# TPS552882_SCH.net
KiCad netlist of a schematic drawn in Altium Designer
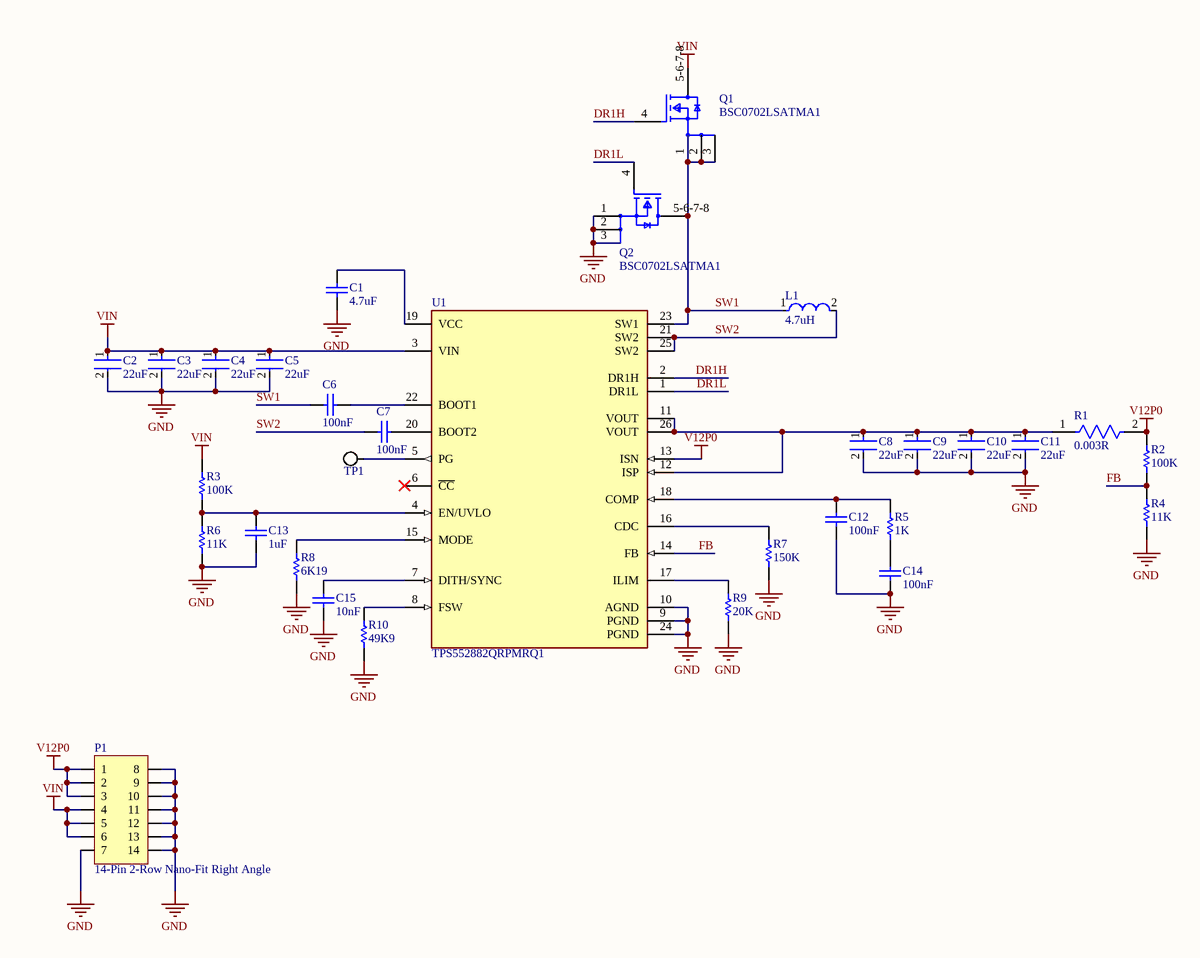
[diagram p0: TPS552882_SCH.SchDoc]

(export (version "E")
  (design (tool "Eeschema 10.0.6"))
  (components
    (comp (ref "C1")
      (value "4.7uF")
      (footprint "CAPC1608X87X35NL15T15")
      (description "C0603C475K8PACTU\r\n4.7uf 0603")
      (fields (field (name "PART NUMBER") "C0603C475K8PACTU") (field (name "MANUFACTURER") "Kemet"))
      (libsource (lib "Altium Content Vault") (part "CAP"))
    )
    (comp (ref "C2")
      (value "22uF")
      (footprint "FP-GRM32E-0_3-0_2-MFG")
      (fields (field (name "VOLTAGE") "25V") (field (name "TOLERANCE") "10%"))
      (libsource (lib "Altium Content Vault") (part "02cd4be3c70576c341d710602a673aa"))
    )
    (comp (ref "C3")
      (value "22uF")
      (footprint "FP-GRM32E-0_3-0_2-MFG")
      (fields (field (name "VOLTAGE") "25V") (field (name "TOLERANCE") "10%"))
      (libsource (lib "Altium Content Vault") (part "02cd4be3c70576c341d710602a673aa"))
    )
    (comp (ref "C4")
      (value "22uF")
      (footprint "FP-GRM32E-0_3-0_2-MFG")
      (fields (field (name "VOLTAGE") "25V") (field (name "TOLERANCE") "10%"))
      (libsource (lib "Altium Content Vault") (part "02cd4be3c70576c341d710602a673aa"))
    )
    (comp (ref "C5")
      (value "22uF")
      (footprint "FP-GRM32E-0_3-0_2-MFG")
      (fields (field (name "VOLTAGE") "25V") (field (name "TOLERANCE") "10%"))
      (libsource (lib "Altium Content Vault") (part "02cd4be3c70576c341d710602a673aa"))
    )
    (comp (ref "C6")
      (value "100nF")
      (footprint "0603")
      (description "CAP 100nF 100V ±10% 0603 (1608 Metric) Thickness 1mm SMD")
      (fields (field (name "TOLERANCE") "Â±10%"))
      (libsource (lib "TAUV-Lib") (part "100nF 0603"))
    )
    (comp (ref "C7")
      (value "100nF")
      (footprint "0603")
      (description "CAP 100nF 100V ±10% 0603 (1608 Metric) Thickness 1mm SMD")
      (fields (field (name "TOLERANCE") "Â±10%"))
      (libsource (lib "TAUV-Lib") (part "100nF 0603"))
    )
    (comp (ref "C8")
      (value "22uF")
      (footprint "FP-GRM32E-0_3-0_2-MFG")
      (fields (field (name "VOLTAGE") "25V") (field (name "TOLERANCE") "10%"))
      (libsource (lib "Altium Content Vault") (part "02cd4be3c70576c341d710602a673aa"))
    )
    (comp (ref "C9")
      (value "22uF")
      (footprint "FP-GRM32E-0_3-0_2-MFG")
      (fields (field (name "VOLTAGE") "25V") (field (name "TOLERANCE") "10%"))
      (libsource (lib "Altium Content Vault") (part "02cd4be3c70576c341d710602a673aa"))
    )
    (comp (ref "C10")
      (value "22uF")
      (footprint "FP-GRM32E-0_3-0_2-MFG")
      (fields (field (name "VOLTAGE") "25V") (field (name "TOLERANCE") "10%"))
      (libsource (lib "Altium Content Vault") (part "02cd4be3c70576c341d710602a673aa"))
    )
    (comp (ref "C11")
      (value "22uF")
      (footprint "FP-GRM32E-0_3-0_2-MFG")
      (fields (field (name "VOLTAGE") "25V") (field (name "TOLERANCE") "10%"))
      (libsource (lib "Altium Content Vault") (part "02cd4be3c70576c341d710602a673aa"))
    )
    (comp (ref "C12")
      (value "100nF")
      (footprint "0603")
      (description "CAP 100nF 100V ±10% 0603 (1608 Metric) Thickness 1mm SMD")
      (fields (field (name "TOLERANCE") "Â±10%"))
      (libsource (lib "TAUV-Lib") (part "100nF 0603"))
    )
    (comp (ref "C13")
      (value "1uF")
      (footprint "0603")
      (description "CAP 1uF 25V ±10% 0603 (1608 Metric) Thickness 1mm SMD")
      (fields (field (name "TOLERANCE") "Â±10%"))
      (libsource (lib "TAUV-Lib") (part "1uF 0603"))
    )
    (comp (ref "C14")
      (value "100nF")
      (footprint "0603")
      (description "CAP 100nF 100V ±10% 0603 (1608 Metric) Thickness 1mm SMD")
      (fields (field (name "TOLERANCE") "Â±10%"))
      (libsource (lib "TAUV-Lib") (part "100nF 0603"))
    )
    (comp (ref "C15")
      (value "10nF")
      (footprint "CAPC1608X90X35ML10T15")
      (fields
        (field (name "VOLTAGE") "50V")
        (field (name "TOLERANCE") "10%")
        (field (name "MANUFACTURER") "Murata")
      )
      (libsource (lib "Altium Content Vault") (part "CAP-NP-2"))
    )
    (comp (ref "L1")
      (value "4.7uH")
      (footprint "FP-IHLP-5050EZ-FP_3_226x4-MFG")
      (description "Commercial Inductors, High Saturation Series 4.7uH 12A 15mΩ 20%\r\nIHLP5050EZER4R7M01")
      (fields (field (name "TOLERANCE") "20%"))
      (libsource (lib "Altium Content Vault") (part "725321dda6339637d4d059423bc1c3c"))
    )
    (comp (ref "P1")
      (value "14-Pin 2-Row Nano-Fit Right Angle")
      (footprint "MOLEX NANO-FIT 2X7 - Right Angle")
      (description "NanoFit Right Hdr TH DR 14Ckt")
      (fields (field (name "PART NUMBER") "105314-1214") (field (name "MANUFACTURER") "Molex"))
      (libsource (lib "TAUV-Lib") (part "14-Pin 2-Row Nano-Fit Right Angle"))
    )
    (comp (ref "Q1")
      (value "BSC0702LSATMA1")
      (footprint "FP-PG-TDSON-8-MFG")
      (description "BSC0702LSATMA1 Transistor MOSFET N-CH 60V 100A 8-Pin TDSON T/R - Tape and Reel")
      (libsource (lib "Altium Content Vault") (part "02f5e2c6ae375491c3e768752663af3"))
    )
    (comp (ref "Q2")
      (value "BSC0702LSATMA1")
      (footprint "FP-PG-TDSON-8-MFG")
      (description "BSC0702LSATMA1 Transistor MOSFET N-CH 60V 100A 8-Pin TDSON T/R - Tape and Reel")
      (libsource (lib "Altium Content Vault") (part "02f5e2c6ae375491c3e768752663af3"))
    )
    (comp (ref "R1")
      (value "0.003R")
      (footprint "FP-CRE2512-R001-R004-MFG")
      (description "RES 0.003 OHM 1% 3W 2512\r\nCRE2512-FZ-R003E-3")
      (fields (field (name "TOLERANCE") "1%"))
      (libsource (lib "Altium Content Vault") (part "1029c3af85768c4190bb7ad29bc67b5"))
    )
    (comp (ref "R2")
      (value "100K")
      (footprint "0603")
      (description "ERJ-3EKF1003V-100k 0603")
      (fields (field (name "PART NUMBER") "ERJ-3EKF1003V") (field (name "MANUFACTURER") "Panasonic"))
      (libsource (lib "TAUV-Lib") (part "100K 0603"))
    )
    (comp (ref "R3")
      (value "100K")
      (footprint "0603")
      (description "ERJ-3EKF1003V-100k 0603")
      (fields (field (name "PART NUMBER") "ERJ-3EKF1003V") (field (name "MANUFACTURER") "Panasonic"))
      (libsource (lib "TAUV-Lib") (part "100K 0603"))
    )
    (comp (ref "R4")
      (value "11K")
      (footprint "RESC1609X50X30ML10T20")
      (description "CRCW060311K0FKEA\r\n11k 0603")
      (fields (field (name "PART NUMBER") "CRCW060311K0FKEA") (field (name "MANUFACTURER") "Vishay Dale"))
      (libsource (lib "Altium Content Vault") (part "RES"))
    )
    (comp (ref "R5")
      (value "1K")
      (footprint "RESC1608X55X30LL15T15")
      (description "ERJ-3EKF1001V\r\n1k 0603")
      (fields (field (name "PART NUMBER") "ERJ-3EKF1001V") (field (name "MANUFACTURER") "Panasonic"))
      (libsource (lib "Altium Content Vault") (part "RES"))
    )
    (comp (ref "R6")
      (value "11K")
      (footprint "RESC1609X50X30ML10T20")
      (description "CRCW060311K0FKEA\r\n11k 0603")
      (fields (field (name "PART NUMBER") "CRCW060311K0FKEA") (field (name "MANUFACTURER") "Vishay Dale"))
      (libsource (lib "Altium Content Vault") (part "RES"))
    )
    (comp (ref "R7")
      (value "150K")
      (footprint "RESC1608X55X30NL15T15")
      (description "ERJ-3EKF1503V\r\n150k 0603")
      (fields (field (name "MANUFACTURER") "Panasonic") (field (name "PART NUMBER") "ERJ-3EKF1503V"))
      (libsource (lib "Altium Content Vault") (part "RES"))
    )
    (comp (ref "R8")
      (value "6K19")
      (footprint "RESC1609X50X30NL10T20")
      (description "CRCW06036K19FKEA\r\n6.19k 0603")
      (fields (field (name "PART NUMBER") "CRCW06036K19FKEA") (field (name "MANUFACTURER") "Vishay Dale"))
      (libsource (lib "Altium Content Vault") (part "RES"))
    )
    (comp (ref "R9")
      (value "20K")
      (footprint "RESC1609X50X30ML10T20")
      (description "CRCW060320K0JNEA\r\n20k 0603")
      (fields (field (name "MANUFACTURER") "Vishay Dale") (field (name "PART NUMBER") "CRCW060320K0JNEA"))
      (libsource (lib "Altium Content Vault") (part "RES"))
    )
    (comp (ref "R10")
      (value "49K9")
      (footprint "RESC1609X55X30ML10T20")
      (description "TNPW060349K9BEEA\r\n49.9k 0603")
      (fields (field (name "PART NUMBER") "TNPW060349K9BEEA") (field (name "MANUFACTURER") "Vishay Dale"))
      (libsource (lib "Altium Content Vault") (part "RES"))
    )
    (comp (ref "TP1")
      (value "Test Point Pad")
      (footprint "Test Point Pad")
      (description "Test point, Pad, 30 mil")
      (libsource (lib "TAUV-Lib") (part "Test Point Pad"))
    )
    (comp (ref "U1")
      (value "TPS552882QRPMRQ1")
      (footprint "FP-RPM0026A-MFG")
      (description "36-V, 16-A BUCK-BOOST CONVERTER,\r\nTPS552882QWRPMRQ1 or TPS552882QRPMRQ1")
      (libsource (lib "Altium Content Vault") (part "87394b5f344f06372ea757b8144a6b8"))
    )
  )
  (nets
    (net (code "1") (name "/DR1H") (class "Default")
      (node (ref "Q1") (pin "4") (pinfunction "Gate_4") (pintype "passive"))
      (node (ref "U1") (pin "2") (pinfunction "DR1H_2") (pintype "passive"))
    )
    (net (code "2") (name "/DR1L") (class "Default")
      (node (ref "Q2") (pin "4") (pinfunction "Gate_4") (pintype "passive"))
      (node (ref "U1") (pin "1") (pinfunction "DR1L_1") (pintype "passive"))
    )
    (net (code "3") (name "/FB") (class "Default")
      (node (ref "R2") (pin "2") (pinfunction "2_2") (pintype "passive"))
      (node (ref "R4") (pin "2") (pinfunction "2_2") (pintype "passive"))
      (node (ref "U1") (pin "14") (pinfunction "FB_14") (pintype "input"))
    )
    (net (code "4") (name "/SW1") (class "Default")
      (node (ref "C6") (pin "2") (pinfunction "2_2") (pintype "passive"))
      (node (ref "L1") (pin "1") (pinfunction "1_1") (pintype "passive"))
      (node (ref "Q1") (pin "1") (pinfunction "Source_1") (pintype "passive"))
      (node (ref "Q1") (pin "2") (pinfunction "Source_2") (pintype "passive"))
      (node (ref "Q1") (pin "3") (pinfunction "Source_3") (pintype "passive"))
      (node (ref "Q2") (pin "5-6-7-8") (pinfunction "Drain_5-6-7-8") (pintype "passive"))
      (node (ref "U1") (pin "23") (pinfunction "SW1_23") (pintype "passive"))
    )
    (net (code "5") (name "/SW2") (class "Default")
      (node (ref "C7") (pin "2") (pinfunction "2_2") (pintype "passive"))
      (node (ref "L1") (pin "2") (pinfunction "2_2") (pintype "passive"))
      (node (ref "U1") (pin "21") (pinfunction "SW2_21") (pintype "passive"))
      (node (ref "U1") (pin "25") (pinfunction "SW2_25") (pintype "passive"))
    )
    (net (code "6") (name "GND") (class "Default")
      (node (ref "C1") (pin "1") (pinfunction "1_1") (pintype "passive"))
      (node (ref "C10") (pin "2") (pinfunction "2_2") (pintype "passive"))
      (node (ref "C11") (pin "2") (pinfunction "2_2") (pintype "passive"))
      (node (ref "C12") (pin "2") (pinfunction "2_2") (pintype "passive"))
      (node (ref "C13") (pin "1") (pinfunction "1_1") (pintype "passive"))
      (node (ref "C14") (pin "2") (pinfunction "2_2") (pintype "passive"))
      (node (ref "C15") (pin "1") (pinfunction "1_1") (pintype "passive"))
      (node (ref "C2") (pin "2") (pinfunction "2_2") (pintype "passive"))
      (node (ref "C3") (pin "2") (pinfunction "2_2") (pintype "passive"))
      (node (ref "C4") (pin "2") (pinfunction "2_2") (pintype "passive"))
      (node (ref "C5") (pin "2") (pinfunction "2_2") (pintype "passive"))
      (node (ref "C8") (pin "2") (pinfunction "2_2") (pintype "passive"))
      (node (ref "C9") (pin "2") (pinfunction "2_2") (pintype "passive"))
      (node (ref "P1") (pin "10") (pinfunction "10_10") (pintype "passive"))
      (node (ref "P1") (pin "11") (pinfunction "11_11") (pintype "passive"))
      (node (ref "P1") (pin "12") (pinfunction "12_12") (pintype "passive"))
      (node (ref "P1") (pin "13") (pinfunction "13_13") (pintype "passive"))
      (node (ref "P1") (pin "14") (pinfunction "14_14") (pintype "passive"))
      (node (ref "P1") (pin "7") (pinfunction "7_7") (pintype "passive"))
      (node (ref "P1") (pin "8") (pinfunction "8_8") (pintype "passive"))
      (node (ref "P1") (pin "9") (pinfunction "9_9") (pintype "passive"))
      (node (ref "Q2") (pin "1") (pinfunction "Source_1") (pintype "passive"))
      (node (ref "Q2") (pin "2") (pinfunction "Source_2") (pintype "passive"))
      (node (ref "Q2") (pin "3") (pinfunction "Source_3") (pintype "passive"))
      (node (ref "R10") (pin "1") (pinfunction "1_1") (pintype "passive"))
      (node (ref "R4") (pin "1") (pinfunction "1_1") (pintype "passive"))
      (node (ref "R6") (pin "1") (pinfunction "1_1") (pintype "passive"))
      (node (ref "R7") (pin "2") (pinfunction "2_2") (pintype "passive"))
      (node (ref "R8") (pin "1") (pinfunction "1_1") (pintype "passive"))
      (node (ref "R9") (pin "2") (pinfunction "2_2") (pintype "passive"))
      (node (ref "U1") (pin "10") (pinfunction "AGND_10") (pintype "power_in"))
      (node (ref "U1") (pin "24") (pinfunction "PGND_24") (pintype "power_in"))
      (node (ref "U1") (pin "9") (pinfunction "PGND_9") (pintype "power_in"))
    )
    (net (code "7") (name "Net-(C14-Pad1)") (class "Default")
      (node (ref "C14") (pin "1") (pinfunction "1_1") (pintype "passive"))
      (node (ref "R5") (pin "1") (pinfunction "1_1") (pintype "passive"))
    )
    (net (code "8") (name "Net-(U1-BOOT1)") (class "Default")
      (node (ref "C6") (pin "1") (pinfunction "1_1") (pintype "passive"))
      (node (ref "U1") (pin "22") (pinfunction "BOOT1_22") (pintype "passive"))
    )
    (net (code "9") (name "Net-(U1-BOOT2)") (class "Default")
      (node (ref "C7") (pin "1") (pinfunction "1_1") (pintype "passive"))
      (node (ref "U1") (pin "20") (pinfunction "BOOT2_20") (pintype "passive"))
    )
    (net (code "10") (name "Net-(U1-CDC)") (class "Default")
      (node (ref "R7") (pin "1") (pinfunction "1_1") (pintype "passive"))
      (node (ref "U1") (pin "16") (pinfunction "CDC_16") (pintype "passive"))
    )
    (net (code "11") (name "Net-(U1-COMP)") (class "Default")
      (node (ref "C12") (pin "1") (pinfunction "1_1") (pintype "passive"))
      (node (ref "R5") (pin "2") (pinfunction "2_2") (pintype "passive"))
      (node (ref "U1") (pin "18") (pinfunction "COMP_18") (pintype "input"))
    )
    (net (code "12") (name "Net-(U1-DITH{slash}SYNC)") (class "Default")
      (node (ref "C15") (pin "2") (pinfunction "2_2") (pintype "passive"))
      (node (ref "U1") (pin "7") (pinfunction "DITH/SYNC_7") (pintype "input"))
    )
    (net (code "13") (name "Net-(U1-EN{slash}UVLO)") (class "Default")
      (node (ref "C13") (pin "2") (pinfunction "2_2") (pintype "passive"))
      (node (ref "R3") (pin "2") (pinfunction "2_2") (pintype "passive"))
      (node (ref "R6") (pin "2") (pinfunction "2_2") (pintype "passive"))
      (node (ref "U1") (pin "4") (pinfunction "EN/UVLO_4") (pintype "input"))
    )
    (net (code "14") (name "Net-(U1-FSW)") (class "Default")
      (node (ref "R10") (pin "2") (pinfunction "2_2") (pintype "passive"))
      (node (ref "U1") (pin "8") (pinfunction "FSW_8") (pintype "input"))
    )
    (net (code "15") (name "Net-(U1-ILIM)") (class "Default")
      (node (ref "R9") (pin "1") (pinfunction "1_1") (pintype "passive"))
      (node (ref "U1") (pin "17") (pinfunction "ILIM_17") (pintype "passive"))
    )
    (net (code "16") (name "Net-(U1-ISP)") (class "Default")
      (node (ref "C10") (pin "1") (pinfunction "1_1") (pintype "passive"))
      (node (ref "C11") (pin "1") (pinfunction "1_1") (pintype "passive"))
      (node (ref "C8") (pin "1") (pinfunction "1_1") (pintype "passive"))
      (node (ref "C9") (pin "1") (pinfunction "1_1") (pintype "passive"))
      (node (ref "R1") (pin "1") (pinfunction "1_1") (pintype "passive"))
      (node (ref "U1") (pin "11") (pinfunction "VOUT_11") (pintype "passive"))
      (node (ref "U1") (pin "12") (pinfunction "ISP_12") (pintype "input"))
      (node (ref "U1") (pin "26") (pinfunction "VOUT_26") (pintype "passive"))
    )
    (net (code "17") (name "Net-(U1-MODE)") (class "Default")
      (node (ref "R8") (pin "2") (pinfunction "2_2") (pintype "passive"))
      (node (ref "U1") (pin "15") (pinfunction "MODE_15") (pintype "input"))
    )
    (net (code "18") (name "Net-(U1-PG)") (class "Default")
      (node (ref "TP1") (pin "1") (pinfunction "1_1") (pintype "passive"))
      (node (ref "U1") (pin "5") (pinfunction "PG_5") (pintype "output"))
    )
    (net (code "19") (name "Net-(U1-VCC)") (class "Default")
      (node (ref "C1") (pin "2") (pinfunction "2_2") (pintype "passive"))
      (node (ref "U1") (pin "19") (pinfunction "VCC_19") (pintype "power_in"))
    )
    (net (code "20") (name "V12P0") (class "Default")
      (node (ref "P1") (pin "1") (pinfunction "1_1") (pintype "passive"))
      (node (ref "P1") (pin "2") (pinfunction "2_2") (pintype "passive"))
      (node (ref "P1") (pin "3") (pinfunction "3_3") (pintype "passive"))
      (node (ref "R1") (pin "2") (pinfunction "2_2") (pintype "passive"))
      (node (ref "R2") (pin "1") (pinfunction "1_1") (pintype "passive"))
      (node (ref "U1") (pin "13") (pinfunction "ISN_13") (pintype "input"))
    )
    (net (code "21") (name "VIN") (class "Default")
      (node (ref "C2") (pin "1") (pinfunction "1_1") (pintype "passive"))
      (node (ref "C3") (pin "1") (pinfunction "1_1") (pintype "passive"))
      (node (ref "C4") (pin "1") (pinfunction "1_1") (pintype "passive"))
      (node (ref "C5") (pin "1") (pinfunction "1_1") (pintype "passive"))
      (node (ref "P1") (pin "4") (pinfunction "4_4") (pintype "passive"))
      (node (ref "P1") (pin "5") (pinfunction "5_5") (pintype "passive"))
      (node (ref "P1") (pin "6") (pinfunction "6_6") (pintype "passive"))
      (node (ref "Q1") (pin "5-6-7-8") (pinfunction "Drain_5-6-7-8") (pintype "passive"))
      (node (ref "R3") (pin "1") (pinfunction "1_1") (pintype "passive"))
      (node (ref "U1") (pin "3") (pinfunction "VIN_3") (pintype "power_in"))
    )
    (net (code "22") (name "unconnected-(U1-~{CC}-Pad6)") (class "Default")
      (node (ref "U1") (pin "6") (pinfunction "~{CC}_6") (pintype "passive+no_connect"))
    )
  )
)
